# bc-led_pwm-universal.net
KiCad netlist of a schematic drawn in EAGLE
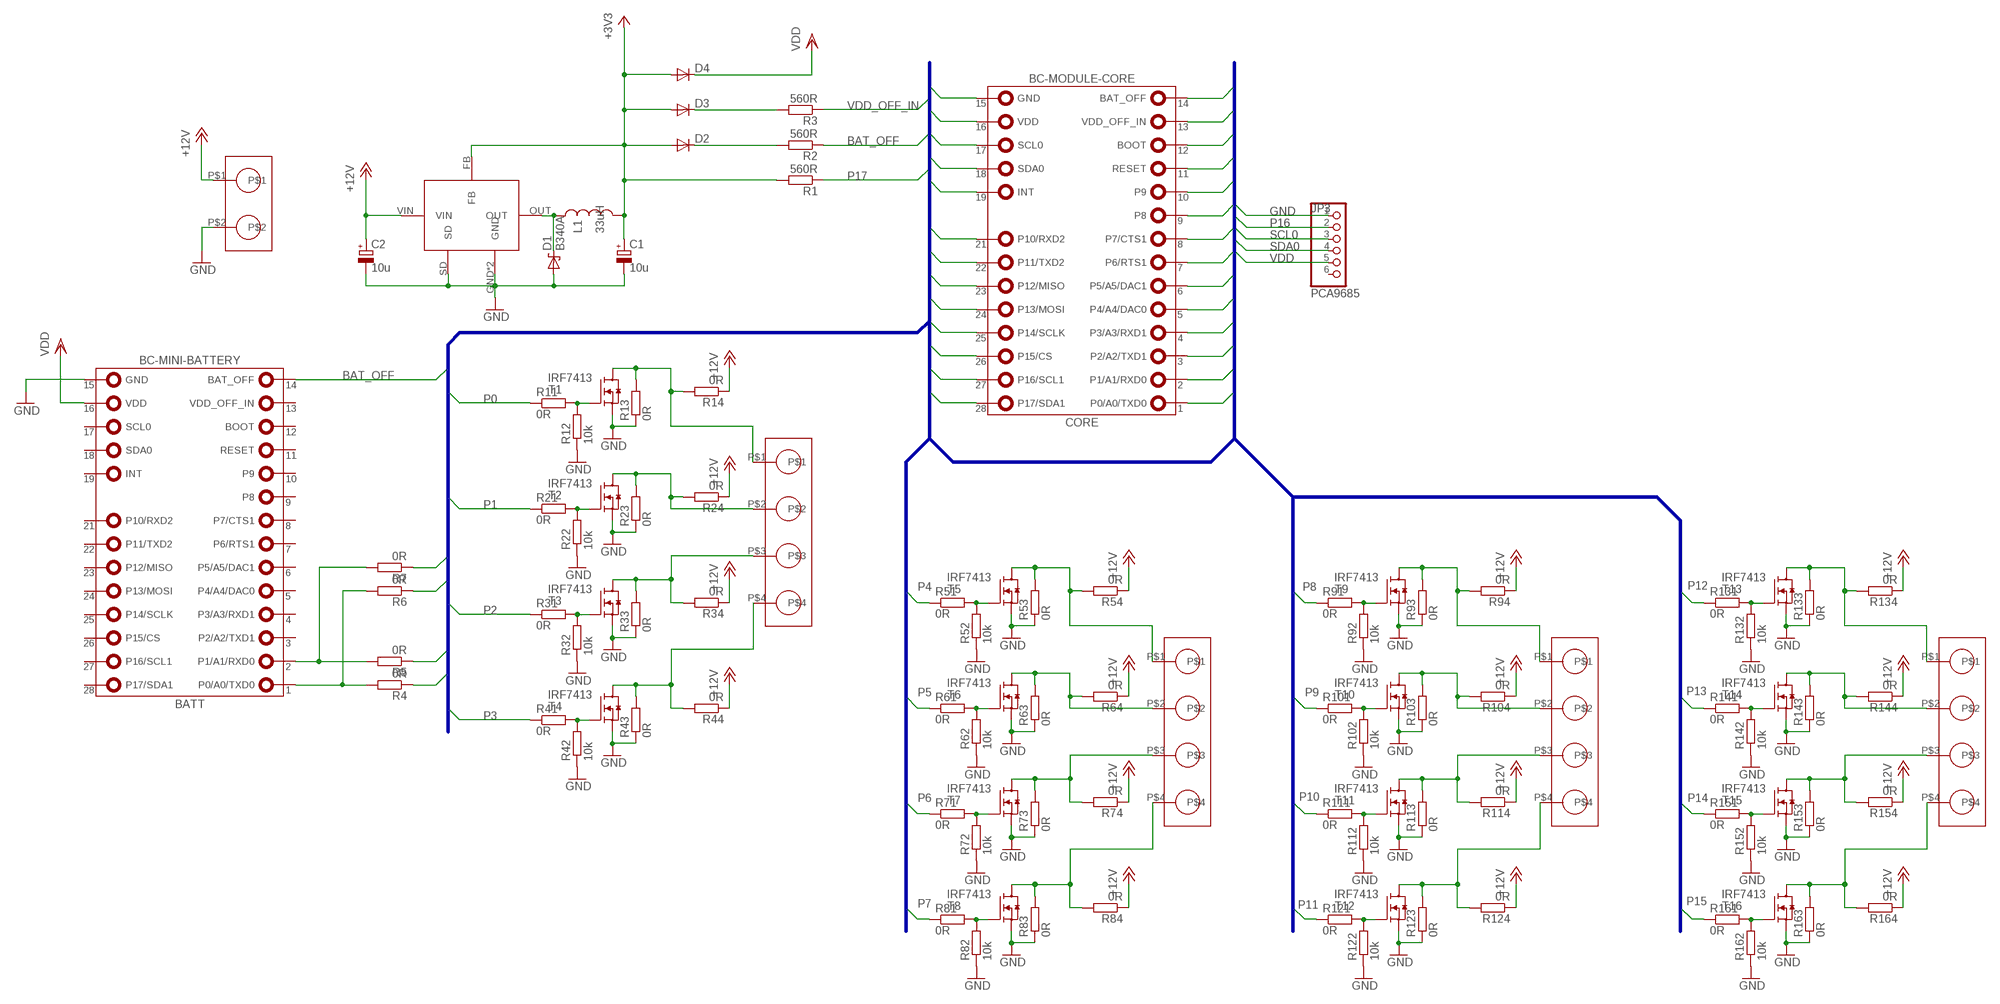
[diagram p0: schematic, sheet 1]

(export (version "E")
  (design (tool "Eeschema 10.0.6"))
  (components
    (comp (ref "BATT")
      (value "BC-MINI-BATTERY")
      (footprint "eagle-import:BC-MODULE-CORE")
      (libsource (lib "eagle-import") (part "BC-MODULE-CORE"))
    )
    (comp (ref "C1")
      (value "10u")
      (footprint "eagle-import:E1,8-4")
      (libsource (lib "eagle-import") (part "CPOL-EUE1.8-4"))
    )
    (comp (ref "C2")
      (value "10u")
      (footprint "eagle-import:E2-5")
      (libsource (lib "eagle-import") (part "CPOL-EUE2-5"))
    )
    (comp (ref "CORE")
      (value "BC-MODULE-CORE")
      (footprint "eagle-import:BC-MODULE-CORE")
      (libsource (lib "eagle-import") (part "BC-MODULE-CORE"))
    )
    (comp (ref "D1")
      (value "B340A")
      (footprint "eagle-import:SMB")
      (libsource (lib "eagle-import") (part "SCHOTTKY-DIODESMD"))
    )
    (comp (ref "D2")
      (value "PMLL41SOD80C")
      (footprint "eagle-import:SOD80C")
      (libsource (lib "eagle-import") (part "PMLL41SOD80C"))
    )
    (comp (ref "D3")
      (value "PMLL41SOD80C")
      (footprint "eagle-import:SOD80C")
      (libsource (lib "eagle-import") (part "PMLL41SOD80C"))
    )
    (comp (ref "D4")
      (value "PMLL41SOD80C")
      (footprint "eagle-import:SOD80C")
      (libsource (lib "eagle-import") (part "PMLL41SOD80C"))
    )
    (comp (ref "JP1")
      (value "STLZ950/2G-5.08-H")
      (footprint "eagle-import:HDR-5.08-1_2")
      (libsource (lib "eagle-import") (part "STLZ950/2G-5.08-H"))
    )
    (comp (ref "JP2A")
      (value "STLZ950/4G-5.08-V")
      (footprint "eagle-import:HDR-5.08-1_4")
      (libsource (lib "eagle-import") (part "STLZ950/4G-5.08-V"))
    )
    (comp (ref "JP2B")
      (value "STLZ950/4G-5.08-V")
      (footprint "eagle-import:HDR-5.08-1_4")
      (libsource (lib "eagle-import") (part "STLZ950/4G-5.08-V"))
    )
    (comp (ref "JP2C")
      (value "STLZ950/4G-5.08-V")
      (footprint "eagle-import:HDR-5.08-1_4")
      (libsource (lib "eagle-import") (part "STLZ950/4G-5.08-V"))
    )
    (comp (ref "JP2D")
      (value "STLZ950/4G-5.08-V")
      (footprint "eagle-import:HDR-5.08-1_4")
      (libsource (lib "eagle-import") (part "STLZ950/4G-5.08-V"))
    )
    (comp (ref "JP3")
      (value "PCA9685")
      (footprint "eagle-import:1X06")
      (libsource (lib "eagle-import") (part "PINHD-1X6"))
    )
    (comp (ref "L1")
      (value "33uH")
      (footprint "eagle-import:BC12")
      (libsource (lib "eagle-import") (part "L-GENERIC-BC12"))
    )
    (comp (ref "R1")
      (value "560R")
      (footprint "eagle-import:R3216")
      (libsource (lib "eagle-import") (part "R-EU_R3216"))
    )
    (comp (ref "R2")
      (value "560R")
      (footprint "eagle-import:R3216")
      (libsource (lib "eagle-import") (part "R-EU_R3216"))
    )
    (comp (ref "R3")
      (value "560R")
      (footprint "eagle-import:R3216")
      (libsource (lib "eagle-import") (part "R-EU_R3216"))
    )
    (comp (ref "R4")
      (value "0R")
      (footprint "eagle-import:R3216")
      (libsource (lib "eagle-import") (part "R-EU_R3216"))
    )
    (comp (ref "R5")
      (value "0R")
      (footprint "eagle-import:R3216")
      (libsource (lib "eagle-import") (part "R-EU_R3216"))
    )
    (comp (ref "R6")
      (value "0R")
      (footprint "eagle-import:R3216")
      (libsource (lib "eagle-import") (part "R-EU_R3216"))
    )
    (comp (ref "R7")
      (value "0R")
      (footprint "eagle-import:R3216")
      (libsource (lib "eagle-import") (part "R-EU_R3216"))
    )
    (comp (ref "R11")
      (value "0R")
      (footprint "eagle-import:0207_7")
      (libsource (lib "eagle-import") (part "R-EU_0207/7"))
    )
    (comp (ref "R12")
      (value "10k")
      (footprint "eagle-import:R3216")
      (libsource (lib "eagle-import") (part "R-EU_R3216"))
    )
    (comp (ref "R13")
      (value "0R")
      (footprint "eagle-import:R3216")
      (libsource (lib "eagle-import") (part "R-EU_R3216"))
    )
    (comp (ref "R14")
      (value "0R")
      (footprint "eagle-import:R3216")
      (libsource (lib "eagle-import") (part "R-EU_R3216"))
    )
    (comp (ref "R21")
      (value "0R")
      (footprint "eagle-import:0207_7")
      (libsource (lib "eagle-import") (part "R-EU_0207/7"))
    )
    (comp (ref "R22")
      (value "10k")
      (footprint "eagle-import:R3216")
      (libsource (lib "eagle-import") (part "R-EU_R3216"))
    )
    (comp (ref "R23")
      (value "0R")
      (footprint "eagle-import:R3216")
      (libsource (lib "eagle-import") (part "R-EU_R3216"))
    )
    (comp (ref "R24")
      (value "0R")
      (footprint "eagle-import:R3216")
      (libsource (lib "eagle-import") (part "R-EU_R3216"))
    )
    (comp (ref "R31")
      (value "0R")
      (footprint "eagle-import:0207_7")
      (libsource (lib "eagle-import") (part "R-EU_0207/7"))
    )
    (comp (ref "R32")
      (value "10k")
      (footprint "eagle-import:R3216")
      (libsource (lib "eagle-import") (part "R-EU_R3216"))
    )
    (comp (ref "R33")
      (value "0R")
      (footprint "eagle-import:R3216")
      (libsource (lib "eagle-import") (part "R-EU_R3216"))
    )
    (comp (ref "R34")
      (value "0R")
      (footprint "eagle-import:R3216")
      (libsource (lib "eagle-import") (part "R-EU_R3216"))
    )
    (comp (ref "R41")
      (value "0R")
      (footprint "eagle-import:0207_7")
      (libsource (lib "eagle-import") (part "R-EU_0207/7"))
    )
    (comp (ref "R42")
      (value "10k")
      (footprint "eagle-import:R3216")
      (libsource (lib "eagle-import") (part "R-EU_R3216"))
    )
    (comp (ref "R43")
      (value "0R")
      (footprint "eagle-import:R3216")
      (libsource (lib "eagle-import") (part "R-EU_R3216"))
    )
    (comp (ref "R44")
      (value "0R")
      (footprint "eagle-import:R3216")
      (libsource (lib "eagle-import") (part "R-EU_R3216"))
    )
    (comp (ref "R51")
      (value "0R")
      (footprint "eagle-import:0207_7")
      (libsource (lib "eagle-import") (part "R-EU_0207/7"))
    )
    (comp (ref "R52")
      (value "10k")
      (footprint "eagle-import:R3216")
      (libsource (lib "eagle-import") (part "R-EU_R3216"))
    )
    (comp (ref "R53")
      (value "0R")
      (footprint "eagle-import:R3216")
      (libsource (lib "eagle-import") (part "R-EU_R3216"))
    )
    (comp (ref "R54")
      (value "0R")
      (footprint "eagle-import:R3216")
      (libsource (lib "eagle-import") (part "R-EU_R3216"))
    )
    (comp (ref "R61")
      (value "0R")
      (footprint "eagle-import:0207_7")
      (libsource (lib "eagle-import") (part "R-EU_0207/7"))
    )
    (comp (ref "R62")
      (value "10k")
      (footprint "eagle-import:R3216")
      (libsource (lib "eagle-import") (part "R-EU_R3216"))
    )
    (comp (ref "R63")
      (value "0R")
      (footprint "eagle-import:R3216")
      (libsource (lib "eagle-import") (part "R-EU_R3216"))
    )
    (comp (ref "R64")
      (value "0R")
      (footprint "eagle-import:R3216")
      (libsource (lib "eagle-import") (part "R-EU_R3216"))
    )
    (comp (ref "R71")
      (value "0R")
      (footprint "eagle-import:0207_7")
      (libsource (lib "eagle-import") (part "R-EU_0207/7"))
    )
    (comp (ref "R72")
      (value "10k")
      (footprint "eagle-import:R3216")
      (libsource (lib "eagle-import") (part "R-EU_R3216"))
    )
    (comp (ref "R73")
      (value "0R")
      (footprint "eagle-import:R3216")
      (libsource (lib "eagle-import") (part "R-EU_R3216"))
    )
    (comp (ref "R74")
      (value "0R")
      (footprint "eagle-import:R3216")
      (libsource (lib "eagle-import") (part "R-EU_R3216"))
    )
    (comp (ref "R81")
      (value "0R")
      (footprint "eagle-import:0207_7")
      (libsource (lib "eagle-import") (part "R-EU_0207/7"))
    )
    (comp (ref "R82")
      (value "10k")
      (footprint "eagle-import:R3216")
      (libsource (lib "eagle-import") (part "R-EU_R3216"))
    )
    (comp (ref "R83")
      (value "0R")
      (footprint "eagle-import:R3216")
      (libsource (lib "eagle-import") (part "R-EU_R3216"))
    )
    (comp (ref "R84")
      (value "0R")
      (footprint "eagle-import:R3216")
      (libsource (lib "eagle-import") (part "R-EU_R3216"))
    )
    (comp (ref "R91")
      (value "0R")
      (footprint "eagle-import:0207_7")
      (libsource (lib "eagle-import") (part "R-EU_0207/7"))
    )
    (comp (ref "R92")
      (value "10k")
      (footprint "eagle-import:R3216")
      (libsource (lib "eagle-import") (part "R-EU_R3216"))
    )
    (comp (ref "R93")
      (value "0R")
      (footprint "eagle-import:R3216")
      (libsource (lib "eagle-import") (part "R-EU_R3216"))
    )
    (comp (ref "R94")
      (value "0R")
      (footprint "eagle-import:R3216")
      (libsource (lib "eagle-import") (part "R-EU_R3216"))
    )
    (comp (ref "R101")
      (value "0R")
      (footprint "eagle-import:0207_7")
      (libsource (lib "eagle-import") (part "R-EU_0207/7"))
    )
    (comp (ref "R102")
      (value "10k")
      (footprint "eagle-import:R3216")
      (libsource (lib "eagle-import") (part "R-EU_R3216"))
    )
    (comp (ref "R103")
      (value "0R")
      (footprint "eagle-import:R3216")
      (libsource (lib "eagle-import") (part "R-EU_R3216"))
    )
    (comp (ref "R104")
      (value "0R")
      (footprint "eagle-import:R3216")
      (libsource (lib "eagle-import") (part "R-EU_R3216"))
    )
    (comp (ref "R111")
      (value "0R")
      (footprint "eagle-import:0207_7")
      (libsource (lib "eagle-import") (part "R-EU_0207/7"))
    )
    (comp (ref "R112")
      (value "10k")
      (footprint "eagle-import:R3216")
      (libsource (lib "eagle-import") (part "R-EU_R3216"))
    )
    (comp (ref "R113")
      (value "0R")
      (footprint "eagle-import:R3216")
      (libsource (lib "eagle-import") (part "R-EU_R3216"))
    )
    (comp (ref "R114")
      (value "0R")
      (footprint "eagle-import:R3216")
      (libsource (lib "eagle-import") (part "R-EU_R3216"))
    )
    (comp (ref "R121")
      (value "0R")
      (footprint "eagle-import:0207_7")
      (libsource (lib "eagle-import") (part "R-EU_0207/7"))
    )
    (comp (ref "R122")
      (value "10k")
      (footprint "eagle-import:R3216")
      (libsource (lib "eagle-import") (part "R-EU_R3216"))
    )
    (comp (ref "R123")
      (value "0R")
      (footprint "eagle-import:R3216")
      (libsource (lib "eagle-import") (part "R-EU_R3216"))
    )
    (comp (ref "R124")
      (value "0R")
      (footprint "eagle-import:R3216")
      (libsource (lib "eagle-import") (part "R-EU_R3216"))
    )
    (comp (ref "R131")
      (value "0R")
      (footprint "eagle-import:0207_7")
      (libsource (lib "eagle-import") (part "R-EU_0207/7"))
    )
    (comp (ref "R132")
      (value "10k")
      (footprint "eagle-import:R3216")
      (libsource (lib "eagle-import") (part "R-EU_R3216"))
    )
    (comp (ref "R133")
      (value "0R")
      (footprint "eagle-import:R3216")
      (libsource (lib "eagle-import") (part "R-EU_R3216"))
    )
    (comp (ref "R134")
      (value "0R")
      (footprint "eagle-import:R3216")
      (libsource (lib "eagle-import") (part "R-EU_R3216"))
    )
    (comp (ref "R141")
      (value "0R")
      (footprint "eagle-import:0207_7")
      (libsource (lib "eagle-import") (part "R-EU_0207/7"))
    )
    (comp (ref "R142")
      (value "10k")
      (footprint "eagle-import:R3216")
      (libsource (lib "eagle-import") (part "R-EU_R3216"))
    )
    (comp (ref "R143")
      (value "0R")
      (footprint "eagle-import:R3216")
      (libsource (lib "eagle-import") (part "R-EU_R3216"))
    )
    (comp (ref "R144")
      (value "0R")
      (footprint "eagle-import:R3216")
      (libsource (lib "eagle-import") (part "R-EU_R3216"))
    )
    (comp (ref "R151")
      (value "0R")
      (footprint "eagle-import:0207_7")
      (libsource (lib "eagle-import") (part "R-EU_0207/7"))
    )
    (comp (ref "R152")
      (value "10k")
      (footprint "eagle-import:R3216")
      (libsource (lib "eagle-import") (part "R-EU_R3216"))
    )
    (comp (ref "R153")
      (value "0R")
      (footprint "eagle-import:R3216")
      (libsource (lib "eagle-import") (part "R-EU_R3216"))
    )
    (comp (ref "R154")
      (value "0R")
      (footprint "eagle-import:R3216")
      (libsource (lib "eagle-import") (part "R-EU_R3216"))
    )
    (comp (ref "R161")
      (value "0R")
      (footprint "eagle-import:0207_7")
      (libsource (lib "eagle-import") (part "R-EU_0207/7"))
    )
    (comp (ref "R162")
      (value "10k")
      (footprint "eagle-import:R3216")
      (libsource (lib "eagle-import") (part "R-EU_R3216"))
    )
    (comp (ref "R163")
      (value "0R")
      (footprint "eagle-import:R3216")
      (libsource (lib "eagle-import") (part "R-EU_R3216"))
    )
    (comp (ref "R164")
      (value "0R")
      (footprint "eagle-import:R3216")
      (libsource (lib "eagle-import") (part "R-EU_R3216"))
    )
    (comp (ref "T1")
      (value "IRF7413")
      (footprint "eagle-import:SO8")
      (libsource (lib "eagle-import") (part "IRF7413"))
    )
    (comp (ref "T2")
      (value "IRF7413")
      (footprint "eagle-import:SO8")
      (libsource (lib "eagle-import") (part "IRF7413"))
    )
    (comp (ref "T3")
      (value "IRF7413")
      (footprint "eagle-import:SO8")
      (libsource (lib "eagle-import") (part "IRF7413"))
    )
    (comp (ref "T4")
      (value "IRF7413")
      (footprint "eagle-import:SO8")
      (libsource (lib "eagle-import") (part "IRF7413"))
    )
    (comp (ref "T5")
      (value "IRF7413")
      (footprint "eagle-import:SO8")
      (libsource (lib "eagle-import") (part "IRF7413"))
    )
    (comp (ref "T6")
      (value "IRF7413")
      (footprint "eagle-import:SO8")
      (libsource (lib "eagle-import") (part "IRF7413"))
    )
    (comp (ref "T7")
      (value "IRF7413")
      (footprint "eagle-import:SO8")
      (libsource (lib "eagle-import") (part "IRF7413"))
    )
    (comp (ref "T8")
      (value "IRF7413")
      (footprint "eagle-import:SO8")
      (libsource (lib "eagle-import") (part "IRF7413"))
    )
    (comp (ref "T9")
      (value "IRF7413")
      (footprint "eagle-import:SO8")
      (libsource (lib "eagle-import") (part "IRF7413"))
    )
    (comp (ref "T10")
      (value "IRF7413")
      (footprint "eagle-import:SO8")
      (libsource (lib "eagle-import") (part "IRF7413"))
    )
    (comp (ref "T11")
      (value "IRF7413")
      (footprint "eagle-import:SO8")
      (libsource (lib "eagle-import") (part "IRF7413"))
    )
    (comp (ref "T12")
      (value "IRF7413")
      (footprint "eagle-import:SO8")
      (libsource (lib "eagle-import") (part "IRF7413"))
    )
    (comp (ref "T13")
      (value "IRF7413")
      (footprint "eagle-import:SO8")
      (libsource (lib "eagle-import") (part "IRF7413"))
    )
    (comp (ref "T14")
      (value "IRF7413")
      (footprint "eagle-import:SO8")
      (libsource (lib "eagle-import") (part "IRF7413"))
    )
    (comp (ref "T15")
      (value "IRF7413")
      (footprint "eagle-import:SO8")
      (libsource (lib "eagle-import") (part "IRF7413"))
    )
    (comp (ref "T16")
      (value "IRF7413")
      (footprint "eagle-import:SO8")
      (libsource (lib "eagle-import") (part "IRF7413"))
    )
    (comp (ref "U$1")
      (value "AP1501")
      (footprint "eagle-import:TO263-5L")
      (libsource (lib "eagle-import") (part "AP1501"))
    )
  )
  (nets
    (net (code "1") (name "+3V3") (class "Default")
      (node (ref "C1") (pin "+") (pinfunction "+_+") (pintype "passive"))
      (node (ref "D2") (pin "A") (pinfunction "A_A") (pintype "passive"))
      (node (ref "D3") (pin "A") (pinfunction "A_A") (pintype "passive"))
      (node (ref "D4") (pin "A") (pinfunction "A_A") (pintype "passive"))
      (node (ref "L1") (pin "2") (pinfunction "2_2") (pintype "passive"))
      (node (ref "R1") (pin "2") (pinfunction "2_2") (pintype "passive"))
      (node (ref "U$1") (pin "FB") (pinfunction "FB_FB") (pintype "bidirectional"))
    )
    (net (code "2") (name "+12V") (class "Default")
      (node (ref "C2") (pin "+") (pinfunction "+_+") (pintype "passive"))
      (node (ref "JP1") (pin "P$1") (pinfunction "P$1_P$1") (pintype "bidirectional"))
      (node (ref "R104") (pin "1") (pinfunction "1_1") (pintype "passive"))
      (node (ref "R114") (pin "1") (pinfunction "1_1") (pintype "passive"))
      (node (ref "R124") (pin "1") (pinfunction "1_1") (pintype "passive"))
      (node (ref "R134") (pin "1") (pinfunction "1_1") (pintype "passive"))
      (node (ref "R14") (pin "1") (pinfunction "1_1") (pintype "passive"))
      (node (ref "R144") (pin "1") (pinfunction "1_1") (pintype "passive"))
      (node (ref "R154") (pin "1") (pinfunction "1_1") (pintype "passive"))
      (node (ref "R164") (pin "1") (pinfunction "1_1") (pintype "passive"))
      (node (ref "R24") (pin "1") (pinfunction "1_1") (pintype "passive"))
      (node (ref "R34") (pin "1") (pinfunction "1_1") (pintype "passive"))
      (node (ref "R44") (pin "1") (pinfunction "1_1") (pintype "passive"))
      (node (ref "R54") (pin "1") (pinfunction "1_1") (pintype "passive"))
      (node (ref "R64") (pin "1") (pinfunction "1_1") (pintype "passive"))
      (node (ref "R74") (pin "1") (pinfunction "1_1") (pintype "passive"))
      (node (ref "R84") (pin "1") (pinfunction "1_1") (pintype "passive"))
      (node (ref "R94") (pin "1") (pinfunction "1_1") (pintype "passive"))
      (node (ref "U$1") (pin "VIN") (pinfunction "VIN_VIN") (pintype "bidirectional"))
    )
    (net (code "3") (name "/BAT_OFF") (class "Default")
      (node (ref "BATT") (pin "14") (pinfunction "BAT_OFF_14") (pintype "passive"))
      (node (ref "CORE") (pin "14") (pinfunction "BAT_OFF_14") (pintype "passive"))
      (node (ref "R2") (pin "1") (pinfunction "1_1") (pintype "passive"))
    )
    (net (code "4") (name "/P0") (class "Default")
      (node (ref "CORE") (pin "1") (pinfunction "P0/A0/TXD0_1") (pintype "passive"))
      (node (ref "R11") (pin "1") (pinfunction "1_1") (pintype "passive"))
      (node (ref "R4") (pin "1") (pinfunction "1_1") (pintype "passive"))
    )
    (net (code "5") (name "/P1") (class "Default")
      (node (ref "CORE") (pin "2") (pinfunction "P1/A1/RXD0_2") (pintype "passive"))
      (node (ref "R21") (pin "1") (pinfunction "1_1") (pintype "passive"))
      (node (ref "R5") (pin "1") (pinfunction "1_1") (pintype "passive"))
    )
    (net (code "6") (name "/P2") (class "Default")
      (node (ref "CORE") (pin "3") (pinfunction "P2/A2/TXD1_3") (pintype "passive"))
      (node (ref "R31") (pin "1") (pinfunction "1_1") (pintype "passive"))
    )
    (net (code "7") (name "/P3") (class "Default")
      (node (ref "CORE") (pin "4") (pinfunction "P3/A3/RXD1_4") (pintype "passive"))
      (node (ref "R41") (pin "1") (pinfunction "1_1") (pintype "passive"))
    )
    (net (code "8") (name "/P4") (class "Default")
      (node (ref "CORE") (pin "5") (pinfunction "P4/A4/DAC0_5") (pintype "passive"))
      (node (ref "R51") (pin "1") (pinfunction "1_1") (pintype "passive"))
      (node (ref "R6") (pin "1") (pinfunction "1_1") (pintype "passive"))
    )
    (net (code "9") (name "/P5") (class "Default")
      (node (ref "CORE") (pin "6") (pinfunction "P5/A5/DAC1_6") (pintype "passive"))
      (node (ref "R61") (pin "1") (pinfunction "1_1") (pintype "passive"))
      (node (ref "R7") (pin "1") (pinfunction "1_1") (pintype "passive"))
    )
    (net (code "10") (name "/P6") (class "Default")
      (node (ref "CORE") (pin "7") (pinfunction "P6/RTS1_7") (pintype "passive"))
      (node (ref "R71") (pin "1") (pinfunction "1_1") (pintype "passive"))
    )
    (net (code "11") (name "/P7") (class "Default")
      (node (ref "CORE") (pin "8") (pinfunction "P7/CTS1_8") (pintype "passive"))
      (node (ref "R81") (pin "1") (pinfunction "1_1") (pintype "passive"))
    )
    (net (code "12") (name "/P8") (class "Default")
      (node (ref "CORE") (pin "9") (pinfunction "P8_9") (pintype "passive"))
      (node (ref "R91") (pin "1") (pinfunction "1_1") (pintype "passive"))
    )
    (net (code "13") (name "/P9") (class "Default")
      (node (ref "CORE") (pin "10") (pinfunction "P9_10") (pintype "passive"))
      (node (ref "R101") (pin "1") (pinfunction "1_1") (pintype "passive"))
    )
    (net (code "14") (name "/P10") (class "Default")
      (node (ref "CORE") (pin "21") (pinfunction "P10/RXD2_21") (pintype "passive"))
      (node (ref "R111") (pin "1") (pinfunction "1_1") (pintype "passive"))
    )
    (net (code "15") (name "/P11") (class "Default")
      (node (ref "CORE") (pin "22") (pinfunction "P11/TXD2_22") (pintype "passive"))
      (node (ref "R121") (pin "1") (pinfunction "1_1") (pintype "passive"))
    )
    (net (code "16") (name "/P12") (class "Default")
      (node (ref "CORE") (pin "23") (pinfunction "P12/MISO_23") (pintype "passive"))
      (node (ref "R131") (pin "1") (pinfunction "1_1") (pintype "passive"))
    )
    (net (code "17") (name "/P13") (class "Default")
      (node (ref "CORE") (pin "24") (pinfunction "P13/MOSI_24") (pintype "passive"))
      (node (ref "R141") (pin "1") (pinfunction "1_1") (pintype "passive"))
    )
    (net (code "18") (name "/P14") (class "Default")
      (node (ref "CORE") (pin "25") (pinfunction "P14/SCLK_25") (pintype "passive"))
      (node (ref "R151") (pin "1") (pinfunction "1_1") (pintype "passive"))
    )
    (net (code "19") (name "/P15") (class "Default")
      (node (ref "CORE") (pin "26") (pinfunction "P15/CS_26") (pintype "passive"))
      (node (ref "R161") (pin "1") (pinfunction "1_1") (pintype "passive"))
    )
    (net (code "20") (name "/P16") (class "Default")
      (node (ref "CORE") (pin "27") (pinfunction "P16/SCL1_27") (pintype "passive"))
      (node (ref "JP3") (pin "2") (pinfunction "2_2") (pintype "passive"))
    )
    (net (code "21") (name "/P17") (class "Default")
      (node (ref "CORE") (pin "28") (pinfunction "P17/SDA1_28") (pintype "passive"))
      (node (ref "R1") (pin "1") (pinfunction "1_1") (pintype "passive"))
    )
    (net (code "22") (name "/SCL0") (class "Default")
      (node (ref "CORE") (pin "17") (pinfunction "SCL0_17") (pintype "passive"))
      (node (ref "JP3") (pin "3") (pinfunction "3_3") (pintype "passive"))
    )
    (net (code "23") (name "/SDA0") (class "Default")
      (node (ref "CORE") (pin "18") (pinfunction "SDA0_18") (pintype "passive"))
      (node (ref "JP3") (pin "4") (pinfunction "4_4") (pintype "passive"))
    )
    (net (code "24") (name "/VDD_OFF_IN") (class "Default")
      (node (ref "CORE") (pin "13") (pinfunction "VDD_OFF_IN_13") (pintype "passive"))
      (node (ref "R3") (pin "1") (pinfunction "1_1") (pintype "passive"))
    )
    (net (code "25") (name "GND") (class "Default")
      (node (ref "BATT") (pin "15") (pinfunction "GND_15") (pintype "passive"))
      (node (ref "C1") (pin "-") (pinfunction "-_-") (pintype "passive"))
      (node (ref "C2") (pin "-") (pinfunction "-_-") (pintype "passive"))
      (node (ref "CORE") (pin "15") (pinfunction "GND_15") (pintype "passive"))
      (node (ref "D1") (pin "A") (pinfunction "A_A") (pintype "passive"))
      (node (ref "JP1") (pin "P$2") (pinfunction "P$2_P$2") (pintype "bidirectional"))
      (node (ref "JP3") (pin "1") (pinfunction "1_1") (pintype "passive"))
      (node (ref "R102") (pin "1") (pinfunction "1_1") (pintype "passive"))
      (node (ref "R103") (pin "1") (pinfunction "1_1") (pintype "passive"))
      (node (ref "R112") (pin "1") (pinfunction "1_1") (pintype "passive"))
      (node (ref "R113") (pin "1") (pinfunction "1_1") (pintype "passive"))
      (node (ref "R12") (pin "1") (pinfunction "1_1") (pintype "passive"))
      (node (ref "R122") (pin "1") (pinfunction "1_1") (pintype "passive"))
      (node (ref "R123") (pin "1") (pinfunction "1_1") (pintype "passive"))
      (node (ref "R13") (pin "1") (pinfunction "1_1") (pintype "passive"))
      (node (ref "R132") (pin "1") (pinfunction "1_1") (pintype "passive"))
      (node (ref "R133") (pin "1") (pinfunction "1_1") (pintype "passive"))
      (node (ref "R142") (pin "1") (pinfunction "1_1") (pintype "passive"))
      (node (ref "R143") (pin "1") (pinfunction "1_1") (pintype "passive"))
      (node (ref "R152") (pin "1") (pinfunction "1_1") (pintype "passive"))
      (node (ref "R153") (pin "1") (pinfunction "1_1") (pintype "passive"))
      (node (ref "R162") (pin "1") (pinfunction "1_1") (pintype "passive"))
      (node (ref "R163") (pin "1") (pinfunction "1_1") (pintype "passive"))
      (node (ref "R22") (pin "1") (pinfunction "1_1") (pintype "passive"))
      (node (ref "R23") (pin "1") (pinfunction "1_1") (pintype "passive"))
      (node (ref "R32") (pin "1") (pinfunction "1_1") (pintype "passive"))
      (node (ref "R33") (pin "1") (pinfunction "1_1") (pintype "passive"))
      (node (ref "R42") (pin "1") (pinfunction "1_1") (pintype "passive"))
      (node (ref "R43") (pin "1") (pinfunction "1_1") (pintype "passive"))
      (node (ref "R52") (pin "1") (pinfunction "1_1") (pintype "passive"))
      (node (ref "R53") (pin "1") (pinfunction "1_1") (pintype "passive"))
      (node (ref "R62") (pin "1") (pinfunction "1_1") (pintype "passive"))
      (node (ref "R63") (pin "1") (pinfunction "1_1") (pintype "passive"))
      (node (ref "R72") (pin "1") (pinfunction "1_1") (pintype "passive"))
      (node (ref "R73") (pin "1") (pinfunction "1_1") (pintype "passive"))
      (node (ref "R82") (pin "1") (pinfunction "1_1") (pintype "passive"))
      (node (ref "R83") (pin "1") (pinfunction "1_1") (pintype "passive"))
      (node (ref "R92") (pin "1") (pinfunction "1_1") (pintype "passive"))
      (node (ref "R93") (pin "1") (pinfunction "1_1") (pintype "passive"))
      (node (ref "T1") (pin "1") (pinfunction "S_1") (pintype "passive"))
      (node (ref "T1") (pin "2") (pinfunction "S_2") (pintype "passive"))
      (node (ref "T1") (pin "3") (pinfunction "S_3") (pintype "passive"))
      (node (ref "T10") (pin "1") (pinfunction "S_1") (pintype "passive"))
      (node (ref "T10") (pin "2") (pinfunction "S_2") (pintype "passive"))
      (node (ref "T10") (pin "3") (pinfunction "S_3") (pintype "passive"))
      (node (ref "T11") (pin "1") (pinfunction "S_1") (pintype "passive"))
      (node (ref "T11") (pin "2") (pinfunction "S_2") (pintype "passive"))
      (node (ref "T11") (pin "3") (pinfunction "S_3") (pintype "passive"))
      (node (ref "T12") (pin "1") (pinfunction "S_1") (pintype "passive"))
      (node (ref "T12") (pin "2") (pinfunction "S_2") (pintype "passive"))
      (node (ref "T12") (pin "3") (pinfunction "S_3") (pintype "passive"))
      (node (ref "T13") (pin "1") (pinfunction "S_1") (pintype "passive"))
      (node (ref "T13") (pin "2") (pinfunction "S_2") (pintype "passive"))
      (node (ref "T13") (pin "3") (pinfunction "S_3") (pintype "passive"))
      (node (ref "T14") (pin "1") (pinfunction "S_1") (pintype "passive"))
      (node (ref "T14") (pin "2") (pinfunction "S_2") (pintype "passive"))
      (node (ref "T14") (pin "3") (pinfunction "S_3") (pintype "passive"))
      (node (ref "T15") (pin "1") (pinfunction "S_1") (pintype "passive"))
      (node (ref "T15") (pin "2") (pinfunction "S_2") (pintype "passive"))
      (node (ref "T15") (pin "3") (pinfunction "S_3") (pintype "passive"))
      (node (ref "T16") (pin "1") (pinfunction "S_1") (pintype "passive"))
      (node (ref "T16") (pin "2") (pinfunction "S_2") (pintype "passive"))
      (node (ref "T16") (pin "3") (pinfunction "S_3") (pintype "passive"))
      (node (ref "T2") (pin "1") (pinfunction "S_1") (pintype "passive"))
      (node (ref "T2") (pin "2") (pinfunction "S_2") (pintype "passive"))
      (node (ref "T2") (pin "3") (pinfunction "S_3") (pintype "passive"))
      (node (ref "T3") (pin "1") (pinfunction "S_1") (pintype "passive"))
      (node (ref "T3") (pin "2") (pinfunction "S_2") (pintype "passive"))
      (node (ref "T3") (pin "3") (pinfunction "S_3") (pintype "passive"))
      (node (ref "T4") (pin "1") (pinfunction "S_1") (pintype "passive"))
      (node (ref "T4") (pin "2") (pinfunction "S_2") (pintype "passive"))
      (node (ref "T4") (pin "3") (pinfunction "S_3") (pintype "passive"))
      (node (ref "T5") (pin "1") (pinfunction "S_1") (pintype "passive"))
      (node (ref "T5") (pin "2") (pinfunction "S_2") (pintype "passive"))
      (node (ref "T5") (pin "3") (pinfunction "S_3") (pintype "passive"))
      (node (ref "T6") (pin "1") (pinfunction "S_1") (pintype "passive"))
      (node (ref "T6") (pin "2") (pinfunction "S_2") (pintype "passive"))
      (node (ref "T6") (pin "3") (pinfunction "S_3") (pintype "passive"))
      (node (ref "T7") (pin "1") (pinfunction "S_1") (pintype "passive"))
      (node (ref "T7") (pin "2") (pinfunction "S_2") (pintype "passive"))
      (node (ref "T7") (pin "3") (pinfunction "S_3") (pintype "passive"))
      (node (ref "T8") (pin "1") (pinfunction "S_1") (pintype "passive"))
      (node (ref "T8") (pin "2") (pinfunction "S_2") (pintype "passive"))
      (node (ref "T8") (pin "3") (pinfunction "S_3") (pintype "passive"))
      (node (ref "T9") (pin "1") (pinfunction "S_1") (pintype "passive"))
      (node (ref "T9") (pin "2") (pinfunction "S_2") (pintype "passive"))
      (node (ref "T9") (pin "3") (pinfunction "S_3") (pintype "passive"))
      (node (ref "U$1") (pin "GND") (pinfunction "GND_GND") (pintype "bidirectional"))
      (node (ref "U$1") (pin "GND2") (pinfunction "GND_GND2") (pintype "bidirectional"))
      (node (ref "U$1") (pin "SD") (pinfunction "SD_SD") (pintype "bidirectional"))
    )
    (net (code "26") (name "Net-(BATT-P0{slash}A0{slash}TXD0)") (class "Default")
      (node (ref "BATT") (pin "1") (pinfunction "P0/A0/TXD0_1") (pintype "passive"))
      (node (ref "R4") (pin "2") (pinfunction "2_2") (pintype "passive"))
      (node (ref "R6") (pin "2") (pinfunction "2_2") (pintype "passive"))
    )
    (net (code "27") (name "Net-(BATT-P1{slash}A1{slash}RXD0)") (class "Default")
      (node (ref "BATT") (pin "2") (pinfunction "P1/A1/RXD0_2") (pintype "passive"))
      (node (ref "R5") (pin "2") (pinfunction "2_2") (pintype "passive"))
      (node (ref "R7") (pin "2") (pinfunction "2_2") (pintype "passive"))
    )
    (net (code "28") (name "Net-(D1-PadC)") (class "Default")
      (node (ref "D1") (pin "C") (pinfunction "C_C") (pintype "passive"))
      (node (ref "L1") (pin "1") (pinfunction "1_1") (pintype "passive"))
      (node (ref "U$1") (pin "OUT") (pinfunction "OUT_OUT") (pintype "bidirectional"))
    )
    (net (code "29") (name "Net-(D2-PadC)") (class "Default")
      (node (ref "D2") (pin "C") (pinfunction "C_C") (pintype "passive"))
      (node (ref "R2") (pin "2") (pinfunction "2_2") (pintype "passive"))
    )
    (net (code "30") (name "Net-(D3-PadC)") (class "Default")
      (node (ref "D3") (pin "C") (pinfunction "C_C") (pintype "passive"))
      (node (ref "R3") (pin "2") (pinfunction "2_2") (pintype "passive"))
    )
    (net (code "31") (name "Net-(JP2A-PadP$1)") (class "Default")
      (node (ref "JP2A") (pin "P$1") (pinfunction "P$1_P$1") (pintype "bidirectional"))
      (node (ref "R13") (pin "2") (pinfunction "2_2") (pintype "passive"))
      (node (ref "R14") (pin "2") (pinfunction "2_2") (pintype "passive"))
      (node (ref "T1") (pin "5") (pinfunction "D_5") (pintype "passive"))
      (node (ref "T1") (pin "6") (pinfunction "D_6") (pintype "passive"))
      (node (ref "T1") (pin "7") (pinfunction "D_7") (pintype "passive"))
      (node (ref "T1") (pin "8") (pinfunction "D_8") (pintype "passive"))
    )
    (net (code "32") (name "Net-(JP2A-PadP$2)") (class "Default")
      (node (ref "JP2A") (pin "P$2") (pinfunction "P$2_P$2") (pintype "bidirectional"))
      (node (ref "R23") (pin "2") (pinfunction "2_2") (pintype "passive"))
      (node (ref "R24") (pin "2") (pinfunction "2_2") (pintype "passive"))
      (node (ref "T2") (pin "5") (pinfunction "D_5") (pintype "passive"))
      (node (ref "T2") (pin "6") (pinfunction "D_6") (pintype "passive"))
      (node (ref "T2") (pin "7") (pinfunction "D_7") (pintype "passive"))
      (node (ref "T2") (pin "8") (pinfunction "D_8") (pintype "passive"))
    )
    (net (code "33") (name "Net-(JP2A-PadP$3)") (class "Default")
      (node (ref "JP2A") (pin "P$3") (pinfunction "P$3_P$3") (pintype "bidirectional"))
      (node (ref "R33") (pin "2") (pinfunction "2_2") (pintype "passive"))
      (node (ref "R34") (pin "2") (pinfunction "2_2") (pintype "passive"))
      (node (ref "T3") (pin "5") (pinfunction "D_5") (pintype "passive"))
      (node (ref "T3") (pin "6") (pinfunction "D_6") (pintype "passive"))
      (node (ref "T3") (pin "7") (pinfunction "D_7") (pintype "passive"))
      (node (ref "T3") (pin "8") (pinfunction "D_8") (pintype "passive"))
    )
    (net (code "34") (name "Net-(JP2A-PadP$4)") (class "Default")
      (node (ref "JP2A") (pin "P$4") (pinfunction "P$4_P$4") (pintype "bidirectional"))
      (node (ref "R43") (pin "2") (pinfunction "2_2") (pintype "passive"))
      (node (ref "R44") (pin "2") (pinfunction "2_2") (pintype "passive"))
      (node (ref "T4") (pin "5") (pinfunction "D_5") (pintype "passive"))
      (node (ref "T4") (pin "6") (pinfunction "D_6") (pintype "passive"))
      (node (ref "T4") (pin "7") (pinfunction "D_7") (pintype "passive"))
      (node (ref "T4") (pin "8") (pinfunction "D_8") (pintype "passive"))
    )
    (net (code "35") (name "Net-(JP2B-PadP$1)") (class "Default")
      (node (ref "JP2B") (pin "P$1") (pinfunction "P$1_P$1") (pintype "bidirectional"))
      (node (ref "R53") (pin "2") (pinfunction "2_2") (pintype "passive"))
      (node (ref "R54") (pin "2") (pinfunction "2_2") (pintype "passive"))
      (node (ref "T5") (pin "5") (pinfunction "D_5") (pintype "passive"))
      (node (ref "T5") (pin "6") (pinfunction "D_6") (pintype "passive"))
      (node (ref "T5") (pin "7") (pinfunction "D_7") (pintype "passive"))
      (node (ref "T5") (pin "8") (pinfunction "D_8") (pintype "passive"))
    )
    (net (code "36") (name "Net-(JP2B-PadP$2)") (class "Default")
      (node (ref "JP2B") (pin "P$2") (pinfunction "P$2_P$2") (pintype "bidirectional"))
      (node (ref "R63") (pin "2") (pinfunction "2_2") (pintype "passive"))
      (node (ref "R64") (pin "2") (pinfunction "2_2") (pintype "passive"))
      (node (ref "T6") (pin "5") (pinfunction "D_5") (pintype "passive"))
      (node (ref "T6") (pin "6") (pinfunction "D_6") (pintype "passive"))
      (node (ref "T6") (pin "7") (pinfunction "D_7") (pintype "passive"))
      (node (ref "T6") (pin "8") (pinfunction "D_8") (pintype "passive"))
    )
    (net (code "37") (name "Net-(JP2B-PadP$3)") (class "Default")
      (node (ref "JP2B") (pin "P$3") (pinfunction "P$3_P$3") (pintype "bidirectional"))
      (node (ref "R73") (pin "2") (pinfunction "2_2") (pintype "passive"))
      (node (ref "R74") (pin "2") (pinfunction "2_2") (pintype "passive"))
      (node (ref "T7") (pin "5") (pinfunction "D_5") (pintype "passive"))
      (node (ref "T7") (pin "6") (pinfunction "D_6") (pintype "passive"))
      (node (ref "T7") (pin "7") (pinfunction "D_7") (pintype "passive"))
      (node (ref "T7") (pin "8") (pinfunction "D_8") (pintype "passive"))
    )
    (net (code "38") (name "Net-(JP2B-PadP$4)") (class "Default")
      (node (ref "JP2B") (pin "P$4") (pinfunction "P$4_P$4") (pintype "bidirectional"))
      (node (ref "R83") (pin "2") (pinfunction "2_2") (pintype "passive"))
      (node (ref "R84") (pin "2") (pinfunction "2_2") (pintype "passive"))
      (node (ref "T8") (pin "5") (pinfunction "D_5") (pintype "passive"))
      (node (ref "T8") (pin "6") (pinfunction "D_6") (pintype "passive"))
      (node (ref "T8") (pin "7") (pinfunction "D_7") (pintype "passive"))
      (node (ref "T8") (pin "8") (pinfunction "D_8") (pintype "passive"))
    )
    (net (code "39") (name "Net-(JP2C-PadP$1)") (class "Default")
      (node (ref "JP2C") (pin "P$1") (pinfunction "P$1_P$1") (pintype "bidirectional"))
      (node (ref "R93") (pin "2") (pinfunction "2_2") (pintype "passive"))
      (node (ref "R94") (pin "2") (pinfunction "2_2") (pintype "passive"))
      (node (ref "T9") (pin "5") (pinfunction "D_5") (pintype "passive"))
      (node (ref "T9") (pin "6") (pinfunction "D_6") (pintype "passive"))
      (node (ref "T9") (pin "7") (pinfunction "D_7") (pintype "passive"))
      (node (ref "T9") (pin "8") (pinfunction "D_8") (pintype "passive"))
    )
    (net (code "40") (name "Net-(JP2C-PadP$2)") (class "Default")
      (node (ref "JP2C") (pin "P$2") (pinfunction "P$2_P$2") (pintype "bidirectional"))
      (node (ref "R103") (pin "2") (pinfunction "2_2") (pintype "passive"))
      (node (ref "R104") (pin "2") (pinfunction "2_2") (pintype "passive"))
      (node (ref "T10") (pin "5") (pinfunction "D_5") (pintype "passive"))
      (node (ref "T10") (pin "6") (pinfunction "D_6") (pintype "passive"))
      (node (ref "T10") (pin "7") (pinfunction "D_7") (pintype "passive"))
      (node (ref "T10") (pin "8") (pinfunction "D_8") (pintype "passive"))
    )
    (net (code "41") (name "Net-(JP2C-PadP$3)") (class "Default")
      (node (ref "JP2C") (pin "P$3") (pinfunction "P$3_P$3") (pintype "bidirectional"))
      (node (ref "R113") (pin "2") (pinfunction "2_2") (pintype "passive"))
      (node (ref "R114") (pin "2") (pinfunction "2_2") (pintype "passive"))
      (node (ref "T11") (pin "5") (pinfunction "D_5") (pintype "passive"))
      (node (ref "T11") (pin "6") (pinfunction "D_6") (pintype "passive"))
      (node (ref "T11") (pin "7") (pinfunction "D_7") (pintype "passive"))
      (node (ref "T11") (pin "8") (pinfunction "D_8") (pintype "passive"))
    )
    (net (code "42") (name "Net-(JP2C-PadP$4)") (class "Default")
      (node (ref "JP2C") (pin "P$4") (pinfunction "P$4_P$4") (pintype "bidirectional"))
      (node (ref "R123") (pin "2") (pinfunction "2_2") (pintype "passive"))
      (node (ref "R124") (pin "2") (pinfunction "2_2") (pintype "passive"))
      (node (ref "T12") (pin "5") (pinfunction "D_5") (pintype "passive"))
      (node (ref "T12") (pin "6") (pinfunction "D_6") (pintype "passive"))
      (node (ref "T12") (pin "7") (pinfunction "D_7") (pintype "passive"))
      (node (ref "T12") (pin "8") (pinfunction "D_8") (pintype "passive"))
    )
    (net (code "43") (name "Net-(JP2D-PadP$1)") (class "Default")
      (node (ref "JP2D") (pin "P$1") (pinfunction "P$1_P$1") (pintype "bidirectional"))
      (node (ref "R133") (pin "2") (pinfunction "2_2") (pintype "passive"))
      (node (ref "R134") (pin "2") (pinfunction "2_2") (pintype "passive"))
      (node (ref "T13") (pin "5") (pinfunction "D_5") (pintype "passive"))
      (node (ref "T13") (pin "6") (pinfunction "D_6") (pintype "passive"))
      (node (ref "T13") (pin "7") (pinfunction "D_7") (pintype "passive"))
      (node (ref "T13") (pin "8") (pinfunction "D_8") (pintype "passive"))
    )
    (net (code "44") (name "Net-(JP2D-PadP$2)") (class "Default")
      (node (ref "JP2D") (pin "P$2") (pinfunction "P$2_P$2") (pintype "bidirectional"))
      (node (ref "R143") (pin "2") (pinfunction "2_2") (pintype "passive"))
      (node (ref "R144") (pin "2") (pinfunction "2_2") (pintype "passive"))
      (node (ref "T14") (pin "5") (pinfunction "D_5") (pintype "passive"))
      (node (ref "T14") (pin "6") (pinfunction "D_6") (pintype "passive"))
      (node (ref "T14") (pin "7") (pinfunction "D_7") (pintype "passive"))
      (node (ref "T14") (pin "8") (pinfunction "D_8") (pintype "passive"))
    )
    (net (code "45") (name "Net-(JP2D-PadP$3)") (class "Default")
      (node (ref "JP2D") (pin "P$3") (pinfunction "P$3_P$3") (pintype "bidirectional"))
      (node (ref "R153") (pin "2") (pinfunction "2_2") (pintype "passive"))
      (node (ref "R154") (pin "2") (pinfunction "2_2") (pintype "passive"))
      (node (ref "T15") (pin "5") (pinfunction "D_5") (pintype "passive"))
      (node (ref "T15") (pin "6") (pinfunction "D_6") (pintype "passive"))
      (node (ref "T15") (pin "7") (pinfunction "D_7") (pintype "passive"))
      (node (ref "T15") (pin "8") (pinfunction "D_8") (pintype "passive"))
    )
    (net (code "46") (name "Net-(JP2D-PadP$4)") (class "Default")
      (node (ref "JP2D") (pin "P$4") (pinfunction "P$4_P$4") (pintype "bidirectional"))
      (node (ref "R163") (pin "2") (pinfunction "2_2") (pintype "passive"))
      (node (ref "R164") (pin "2") (pinfunction "2_2") (pintype "passive"))
      (node (ref "T16") (pin "5") (pinfunction "D_5") (pintype "passive"))
      (node (ref "T16") (pin "6") (pinfunction "D_6") (pintype "passive"))
      (node (ref "T16") (pin "7") (pinfunction "D_7") (pintype "passive"))
      (node (ref "T16") (pin "8") (pinfunction "D_8") (pintype "passive"))
    )
    (net (code "47") (name "Net-(T1-G)") (class "Default")
      (node (ref "R11") (pin "2") (pinfunction "2_2") (pintype "passive"))
      (node (ref "R12") (pin "2") (pinfunction "2_2") (pintype "passive"))
      (node (ref "T1") (pin "4") (pinfunction "G_4") (pintype "passive"))
    )
    (net (code "48") (name "Net-(T2-G)") (class "Default")
      (node (ref "R21") (pin "2") (pinfunction "2_2") (pintype "passive"))
      (node (ref "R22") (pin "2") (pinfunction "2_2") (pintype "passive"))
      (node (ref "T2") (pin "4") (pinfunction "G_4") (pintype "passive"))
    )
    (net (code "49") (name "Net-(T3-G)") (class "Default")
      (node (ref "R31") (pin "2") (pinfunction "2_2") (pintype "passive"))
      (node (ref "R32") (pin "2") (pinfunction "2_2") (pintype "passive"))
      (node (ref "T3") (pin "4") (pinfunction "G_4") (pintype "passive"))
    )
    (net (code "50") (name "Net-(T4-G)") (class "Default")
      (node (ref "R41") (pin "2") (pinfunction "2_2") (pintype "passive"))
      (node (ref "R42") (pin "2") (pinfunction "2_2") (pintype "passive"))
      (node (ref "T4") (pin "4") (pinfunction "G_4") (pintype "passive"))
    )
    (net (code "51") (name "Net-(T5-G)") (class "Default")
      (node (ref "R51") (pin "2") (pinfunction "2_2") (pintype "passive"))
      (node (ref "R52") (pin "2") (pinfunction "2_2") (pintype "passive"))
      (node (ref "T5") (pin "4") (pinfunction "G_4") (pintype "passive"))
    )
    (net (code "52") (name "Net-(T6-G)") (class "Default")
      (node (ref "R61") (pin "2") (pinfunction "2_2") (pintype "passive"))
      (node (ref "R62") (pin "2") (pinfunction "2_2") (pintype "passive"))
      (node (ref "T6") (pin "4") (pinfunction "G_4") (pintype "passive"))
    )
    (net (code "53") (name "Net-(T7-G)") (class "Default")
      (node (ref "R71") (pin "2") (pinfunction "2_2") (pintype "passive"))
      (node (ref "R72") (pin "2") (pinfunction "2_2") (pintype "passive"))
      (node (ref "T7") (pin "4") (pinfunction "G_4") (pintype "passive"))
    )
    (net (code "54") (name "Net-(T8-G)") (class "Default")
      (node (ref "R81") (pin "2") (pinfunction "2_2") (pintype "passive"))
      (node (ref "R82") (pin "2") (pinfunction "2_2") (pintype "passive"))
      (node (ref "T8") (pin "4") (pinfunction "G_4") (pintype "passive"))
    )
    (net (code "55") (name "Net-(T9-G)") (class "Default")
      (node (ref "R91") (pin "2") (pinfunction "2_2") (pintype "passive"))
      (node (ref "R92") (pin "2") (pinfunction "2_2") (pintype "passive"))
      (node (ref "T9") (pin "4") (pinfunction "G_4") (pintype "passive"))
    )
    (net (code "56") (name "Net-(T10-G)") (class "Default")
      (node (ref "R101") (pin "2") (pinfunction "2_2") (pintype "passive"))
      (node (ref "R102") (pin "2") (pinfunction "2_2") (pintype "passive"))
      (node (ref "T10") (pin "4") (pinfunction "G_4") (pintype "passive"))
    )
    (net (code "57") (name "Net-(T11-G)") (class "Default")
      (node (ref "R111") (pin "2") (pinfunction "2_2") (pintype "passive"))
      (node (ref "R112") (pin "2") (pinfunction "2_2") (pintype "passive"))
      (node (ref "T11") (pin "4") (pinfunction "G_4") (pintype "passive"))
    )
    (net (code "58") (name "Net-(T12-G)") (class "Default")
      (node (ref "R121") (pin "2") (pinfunction "2_2") (pintype "passive"))
      (node (ref "R122") (pin "2") (pinfunction "2_2") (pintype "passive"))
      (node (ref "T12") (pin "4") (pinfunction "G_4") (pintype "passive"))
    )
    (net (code "59") (name "Net-(T13-G)") (class "Default")
      (node (ref "R131") (pin "2") (pinfunction "2_2") (pintype "passive"))
      (node (ref "R132") (pin "2") (pinfunction "2_2") (pintype "passive"))
      (node (ref "T13") (pin "4") (pinfunction "G_4") (pintype "passive"))
    )
    (net (code "60") (name "Net-(T14-G)") (class "Default")
      (node (ref "R141") (pin "2") (pinfunction "2_2") (pintype "passive"))
      (node (ref "R142") (pin "2") (pinfunction "2_2") (pintype "passive"))
      (node (ref "T14") (pin "4") (pinfunction "G_4") (pintype "passive"))
    )
    (net (code "61") (name "Net-(T15-G)") (class "Default")
      (node (ref "R151") (pin "2") (pinfunction "2_2") (pintype "passive"))
      (node (ref "R152") (pin "2") (pinfunction "2_2") (pintype "passive"))
      (node (ref "T15") (pin "4") (pinfunction "G_4") (pintype "passive"))
    )
    (net (code "62") (name "Net-(T16-G)") (class "Default")
      (node (ref "R161") (pin "2") (pinfunction "2_2") (pintype "passive"))
      (node (ref "R162") (pin "2") (pinfunction "2_2") (pintype "passive"))
      (node (ref "T16") (pin "4") (pinfunction "G_4") (pintype "passive"))
    )
    (net (code "63") (name "VDD") (class "Default")
      (node (ref "BATT") (pin "16") (pinfunction "VDD_16") (pintype "passive"))
      (node (ref "CORE") (pin "16") (pinfunction "VDD_16") (pintype "passive"))
      (node (ref "D4") (pin "C") (pinfunction "C_C") (pintype "passive"))
      (node (ref "JP3") (pin "5") (pinfunction "5_5") (pintype "passive"))
    )
    (net (code "64") (name "unconnected-(BATT-BOOT-Pad12)") (class "Default")
      (node (ref "BATT") (pin "12") (pinfunction "BOOT_12") (pintype "passive"))
    )
    (net (code "65") (name "unconnected-(BATT-INT-Pad19)") (class "Default")
      (node (ref "BATT") (pin "19") (pinfunction "INT_19") (pintype "passive"))
    )
    (net (code "66") (name "unconnected-(BATT-P2{slash}A2{slash}TXD1-Pad3)") (class "Default")
      (node (ref "BATT") (pin "3") (pinfunction "P2/A2/TXD1_3") (pintype "passive"))
    )
    (net (code "67") (name "unconnected-(BATT-P3{slash}A3{slash}RXD1-Pad4)") (class "Default")
      (node (ref "BATT") (pin "4") (pinfunction "P3/A3/RXD1_4") (pintype "passive"))
    )
    (net (code "68") (name "unconnected-(BATT-P4{slash}A4{slash}DAC0-Pad5)") (class "Default")
      (node (ref "BATT") (pin "5") (pinfunction "P4/A4/DAC0_5") (pintype "passive"))
    )
    (net (code "69") (name "unconnected-(BATT-P5{slash}A5{slash}DAC1-Pad6)") (class "Default")
      (node (ref "BATT") (pin "6") (pinfunction "P5/A5/DAC1_6") (pintype "passive"))
    )
    (net (code "70") (name "unconnected-(BATT-P6{slash}RTS1-Pad7)") (class "Default")
      (node (ref "BATT") (pin "7") (pinfunction "P6/RTS1_7") (pintype "passive"))
    )
    (net (code "71") (name "unconnected-(BATT-P7{slash}CTS1-Pad8)") (class "Default")
      (node (ref "BATT") (pin "8") (pinfunction "P7/CTS1_8") (pintype "passive"))
    )
    (net (code "72") (name "unconnected-(BATT-P8-Pad9)") (class "Default")
      (node (ref "BATT") (pin "9") (pinfunction "P8_9") (pintype "passive"))
    )
    (net (code "73") (name "unconnected-(BATT-P9-Pad10)") (class "Default")
      (node (ref "BATT") (pin "10") (pinfunction "P9_10") (pintype "passive"))
    )
    (net (code "74") (name "unconnected-(BATT-P10{slash}RXD2-Pad21)") (class "Default")
      (node (ref "BATT") (pin "21") (pinfunction "P10/RXD2_21") (pintype "passive"))
    )
    (net (code "75") (name "unconnected-(BATT-P11{slash}TXD2-Pad22)") (class "Default")
      (node (ref "BATT") (pin "22") (pinfunction "P11/TXD2_22") (pintype "passive"))
    )
    (net (code "76") (name "unconnected-(BATT-P12{slash}MISO-Pad23)") (class "Default")
      (node (ref "BATT") (pin "23") (pinfunction "P12/MISO_23") (pintype "passive"))
    )
    (net (code "77") (name "unconnected-(BATT-P13{slash}MOSI-Pad24)") (class "Default")
      (node (ref "BATT") (pin "24") (pinfunction "P13/MOSI_24") (pintype "passive"))
    )
    (net (code "78") (name "unconnected-(BATT-P14{slash}SCLK-Pad25)") (class "Default")
      (node (ref "BATT") (pin "25") (pinfunction "P14/SCLK_25") (pintype "passive"))
    )
    (net (code "79") (name "unconnected-(BATT-P15{slash}CS-Pad26)") (class "Default")
      (node (ref "BATT") (pin "26") (pinfunction "P15/CS_26") (pintype "passive"))
    )
    (net (code "80") (name "unconnected-(BATT-P16{slash}SCL1-Pad27)") (class "Default")
      (node (ref "BATT") (pin "27") (pinfunction "P16/SCL1_27") (pintype "passive"))
    )
    (net (code "81") (name "unconnected-(BATT-P17{slash}SDA1-Pad28)") (class "Default")
      (node (ref "BATT") (pin "28") (pinfunction "P17/SDA1_28") (pintype "passive"))
    )
    (net (code "82") (name "unconnected-(BATT-RESET-Pad11)") (class "Default")
      (node (ref "BATT") (pin "11") (pinfunction "RESET_11") (pintype "passive"))
    )
    (net (code "83") (name "unconnected-(BATT-SCL0-Pad17)") (class "Default")
      (node (ref "BATT") (pin "17") (pinfunction "SCL0_17") (pintype "passive"))
    )
    (net (code "84") (name "unconnected-(BATT-SDA0-Pad18)") (class "Default")
      (node (ref "BATT") (pin "18") (pinfunction "SDA0_18") (pintype "passive"))
    )
    (net (code "85") (name "unconnected-(BATT-VDD_OFF_IN-Pad13)") (class "Default")
      (node (ref "BATT") (pin "13") (pinfunction "VDD_OFF_IN_13") (pintype "passive"))
    )
    (net (code "86") (name "unconnected-(CORE-BOOT-Pad12)") (class "Default")
      (node (ref "CORE") (pin "12") (pinfunction "BOOT_12") (pintype "passive"))
    )
    (net (code "87") (name "unconnected-(CORE-INT-Pad19)") (class "Default")
      (node (ref "CORE") (pin "19") (pinfunction "INT_19") (pintype "passive"))
    )
    (net (code "88") (name "unconnected-(CORE-RESET-Pad11)") (class "Default")
      (node (ref "CORE") (pin "11") (pinfunction "RESET_11") (pintype "passive"))
    )
    (net (code "89") (name "unconnected-(JP3-Pad6)") (class "Default")
      (node (ref "JP3") (pin "6") (pinfunction "6_6") (pintype "passive"))
    )
  )
)
